# DCF77_RX_1V0.net
KiCad netlist of a schematic drawn in EAGLE
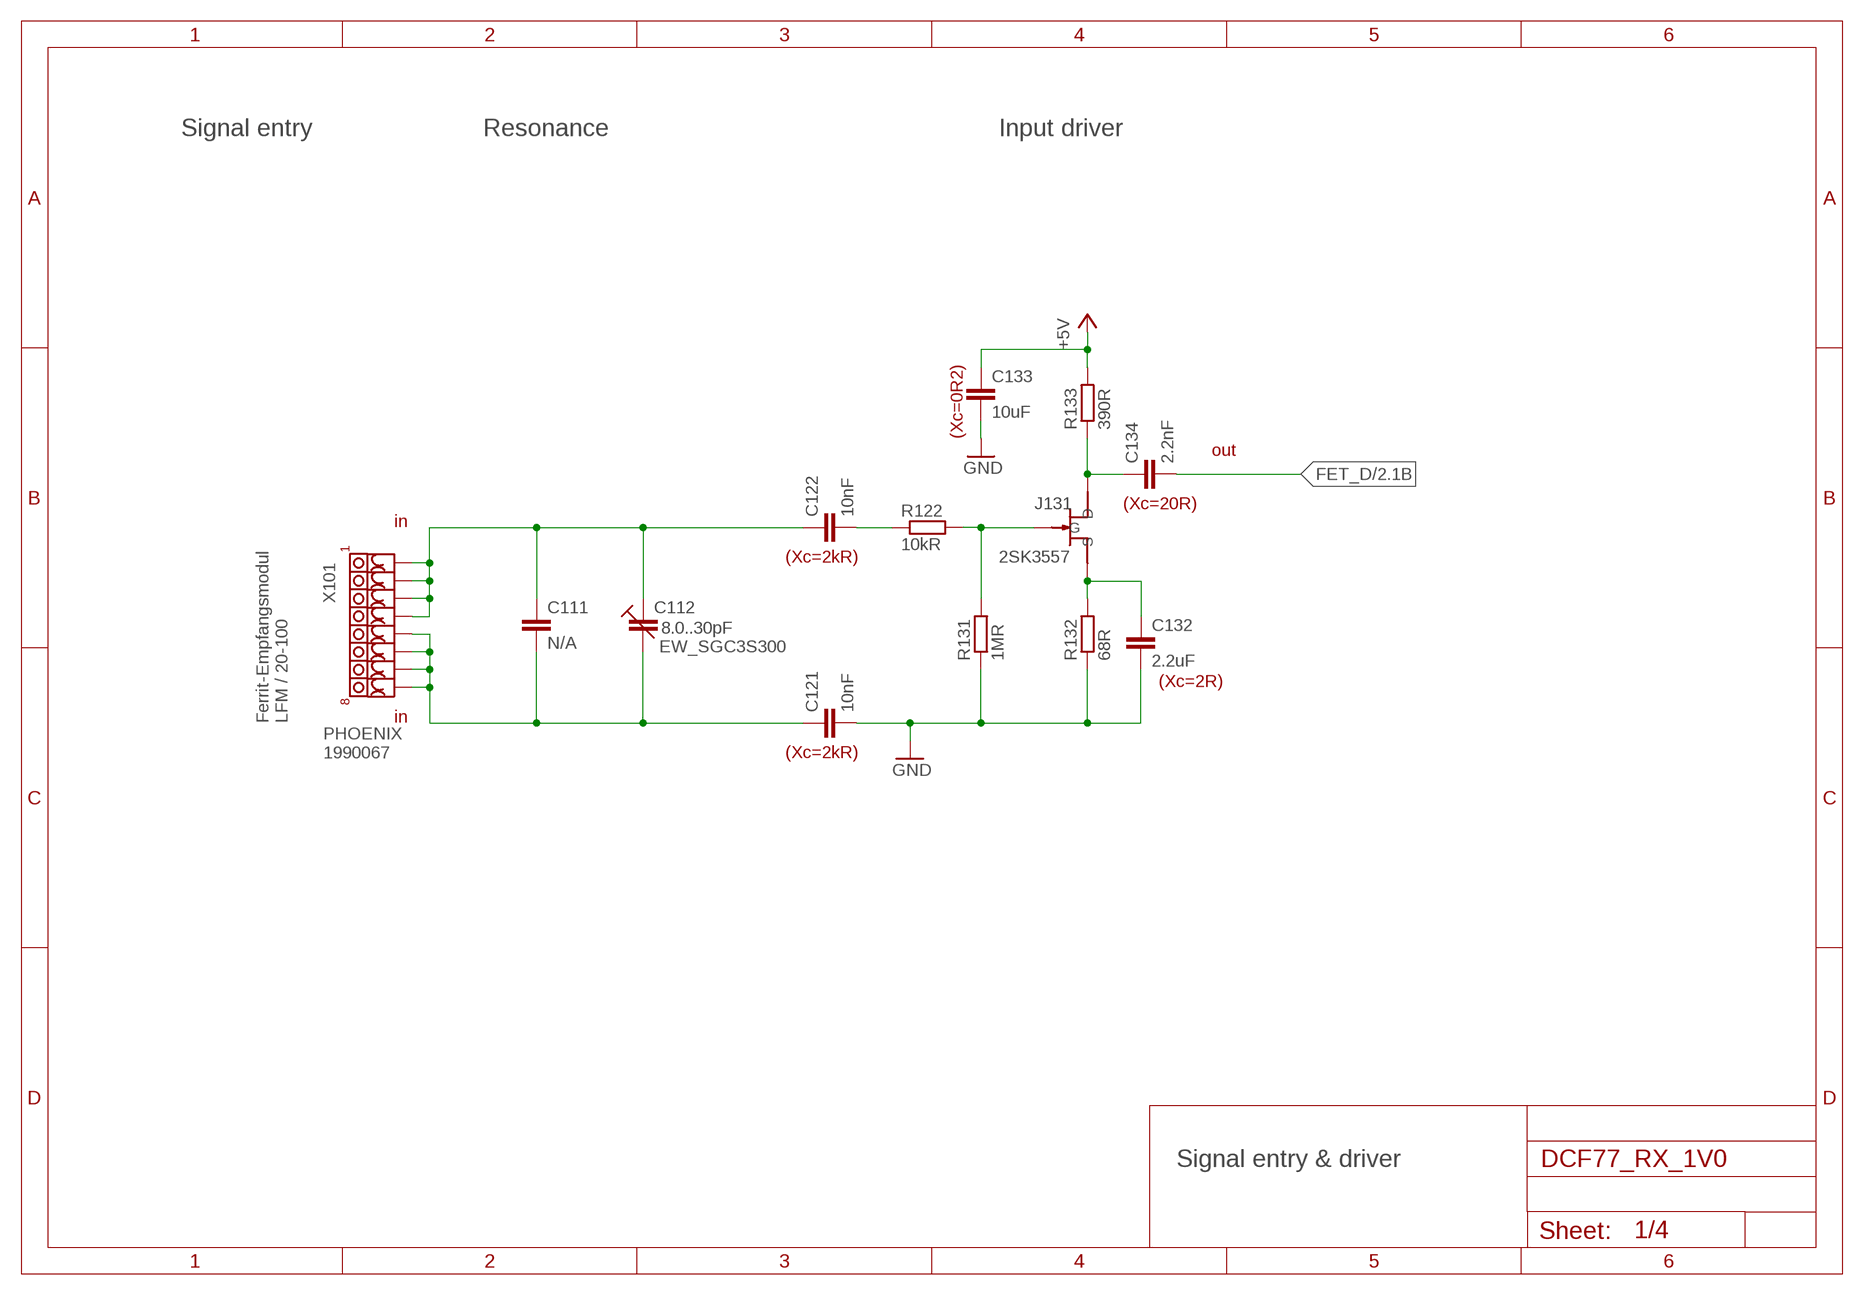
[diagram p0: schematic, sheet 1]
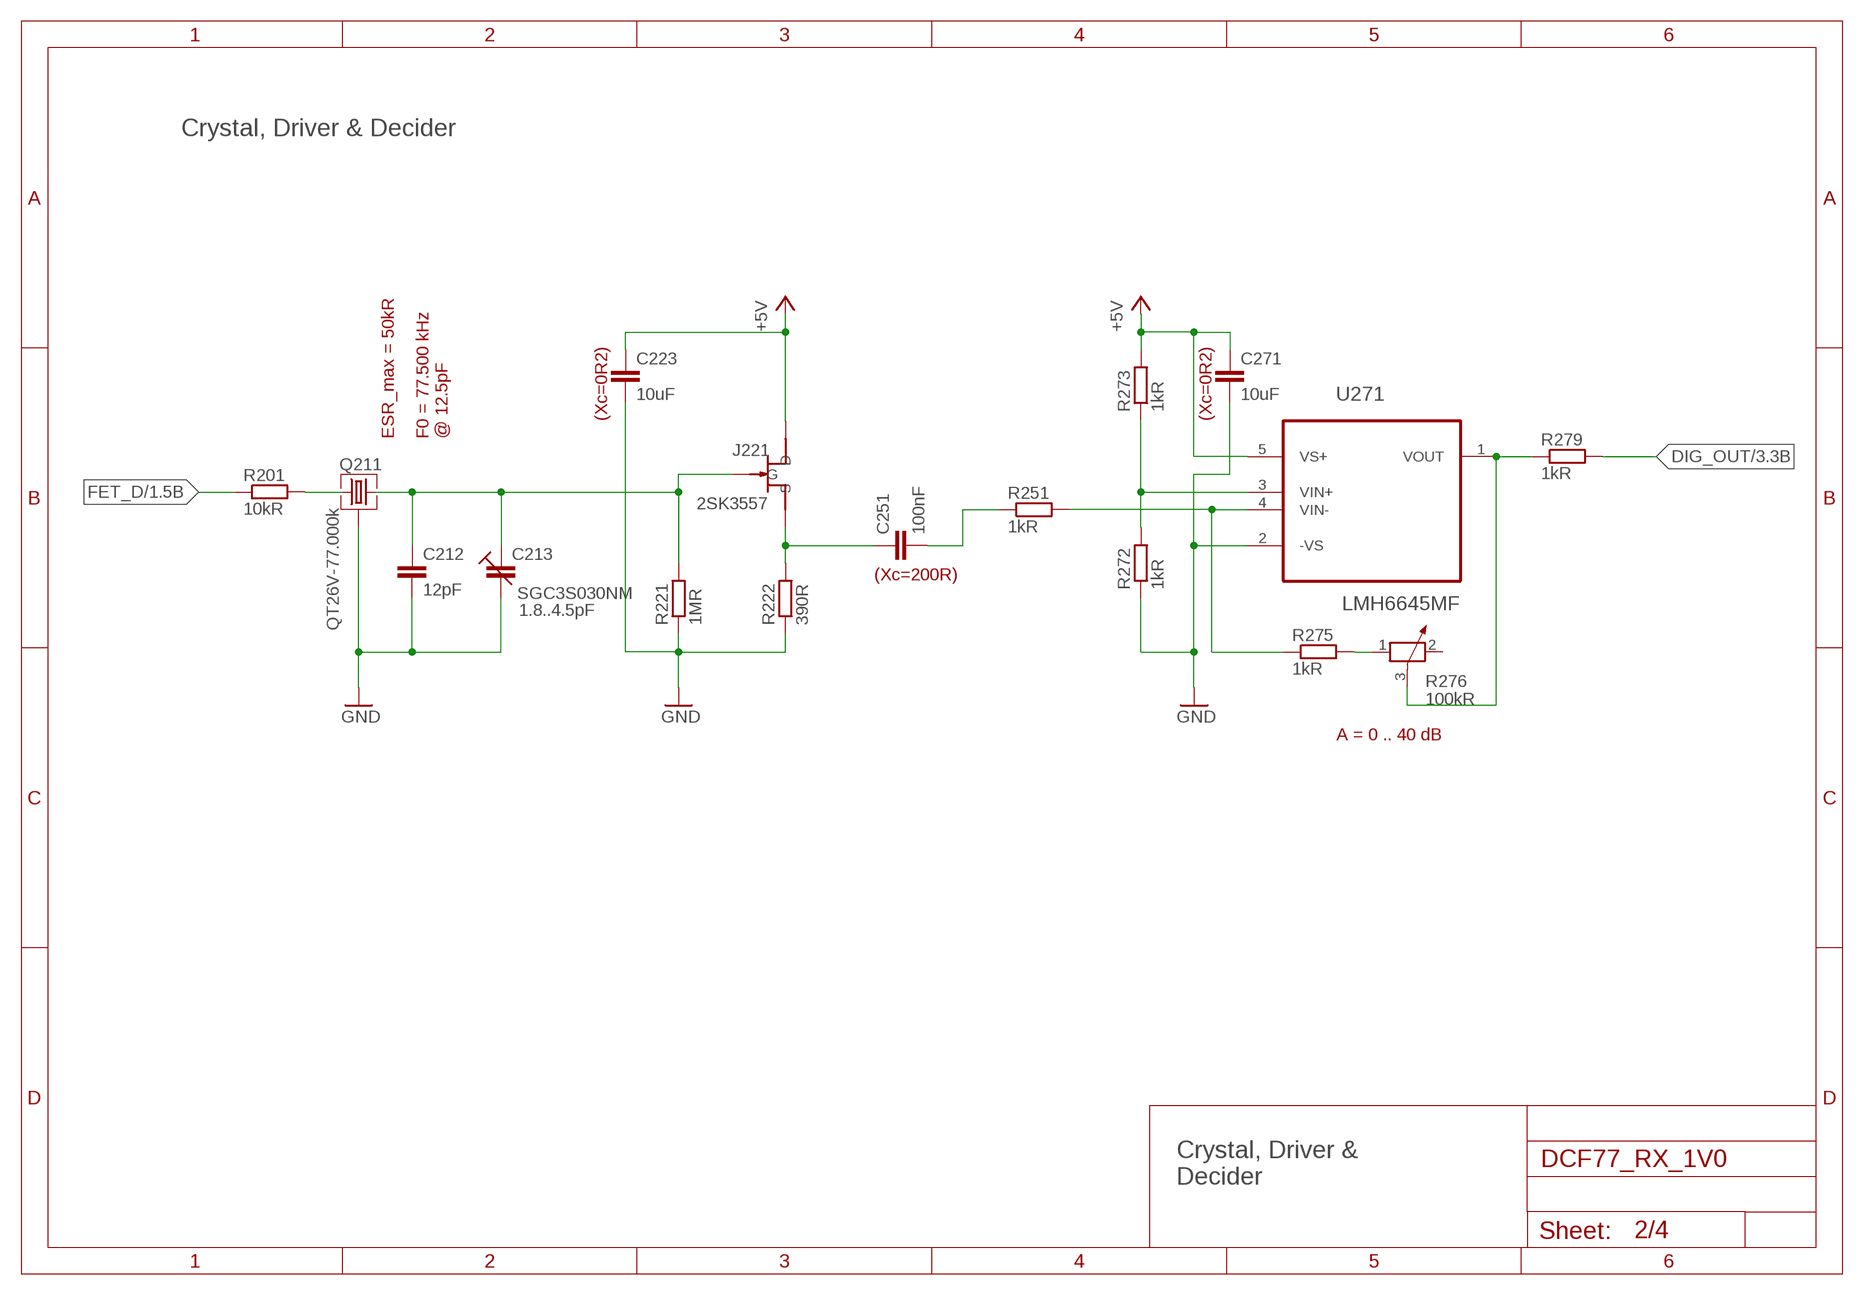
[diagram p1: schematic, sheet 2]
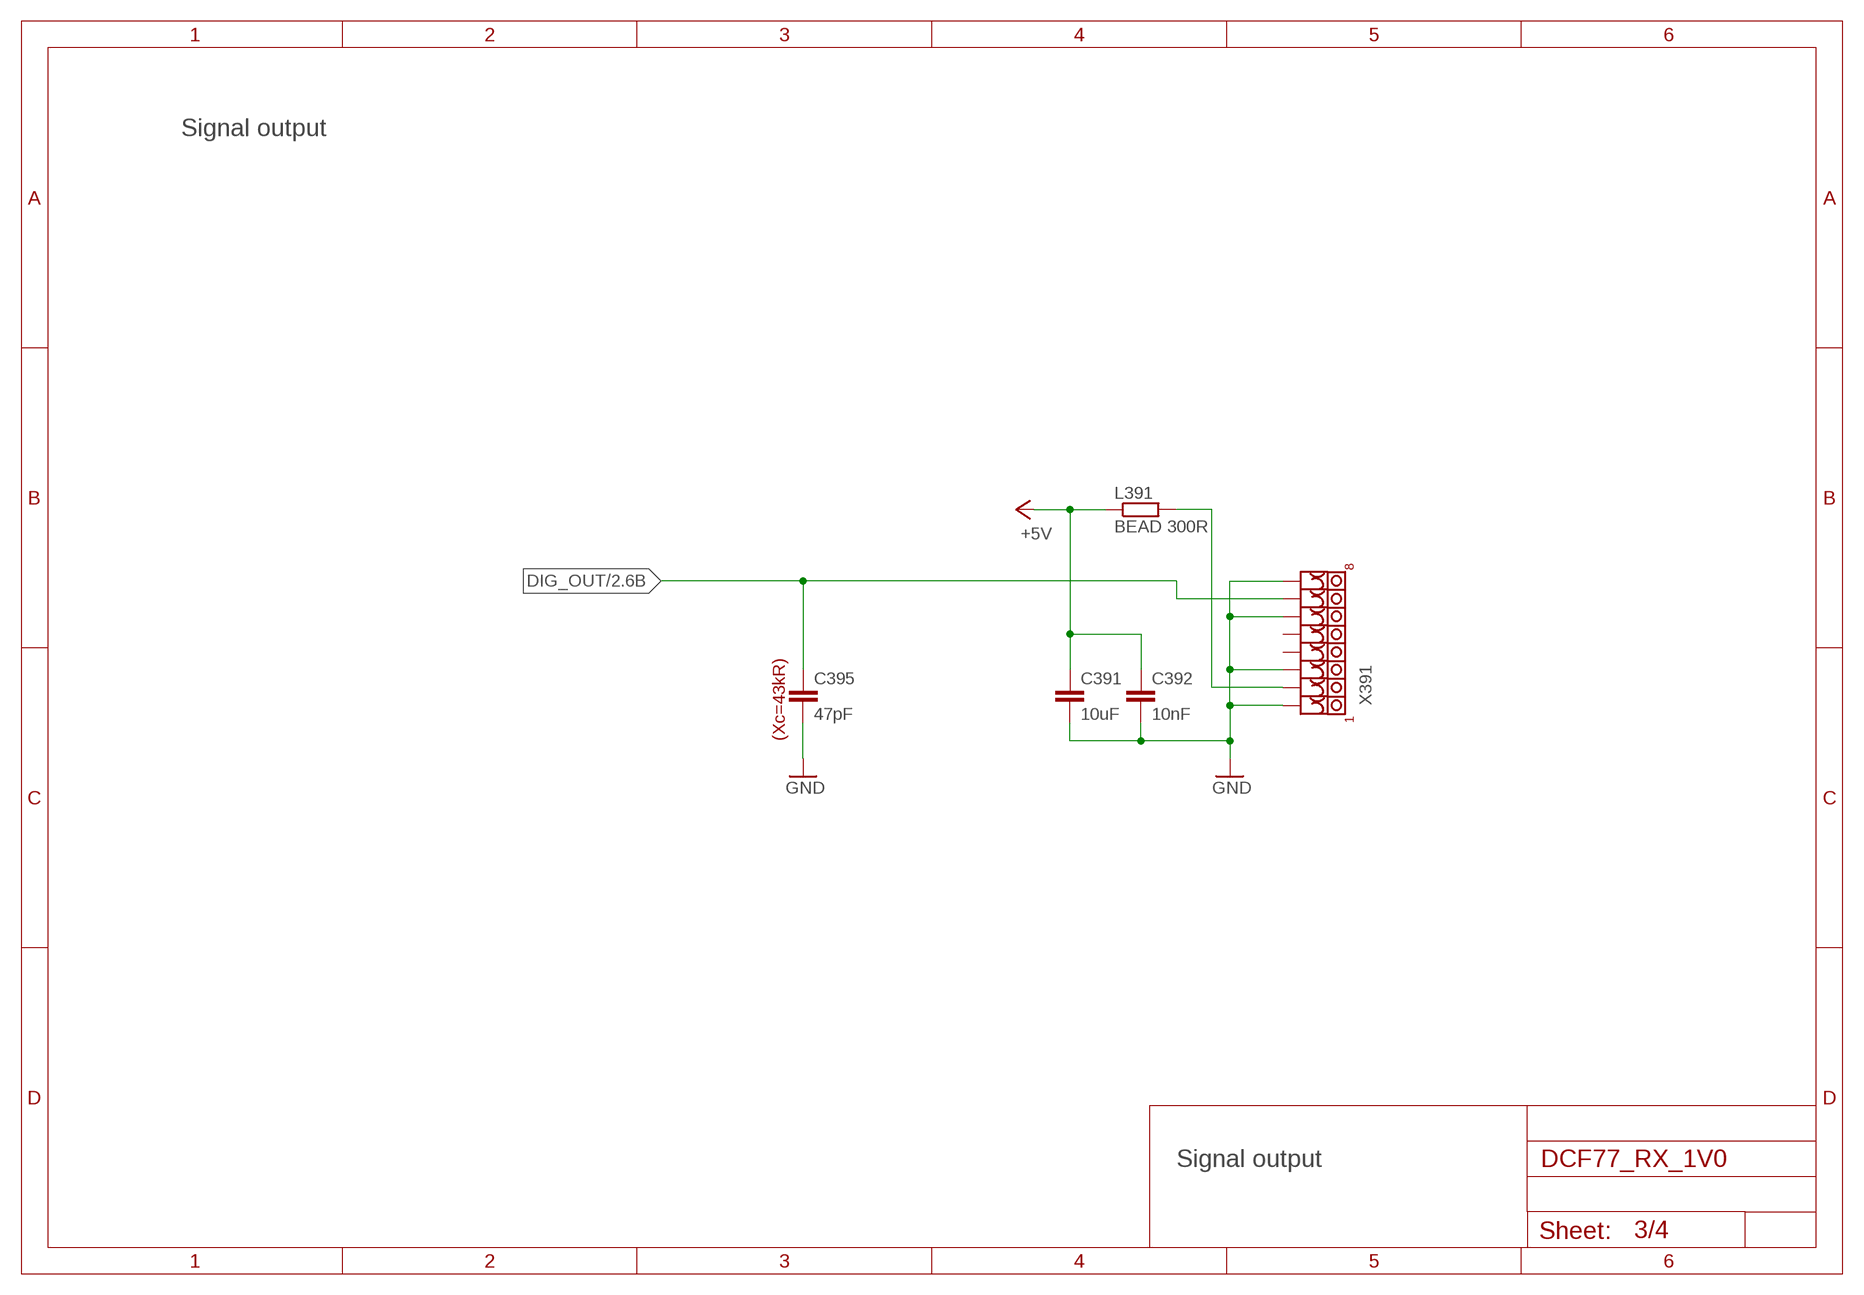
[diagram p2: schematic, sheet 3]
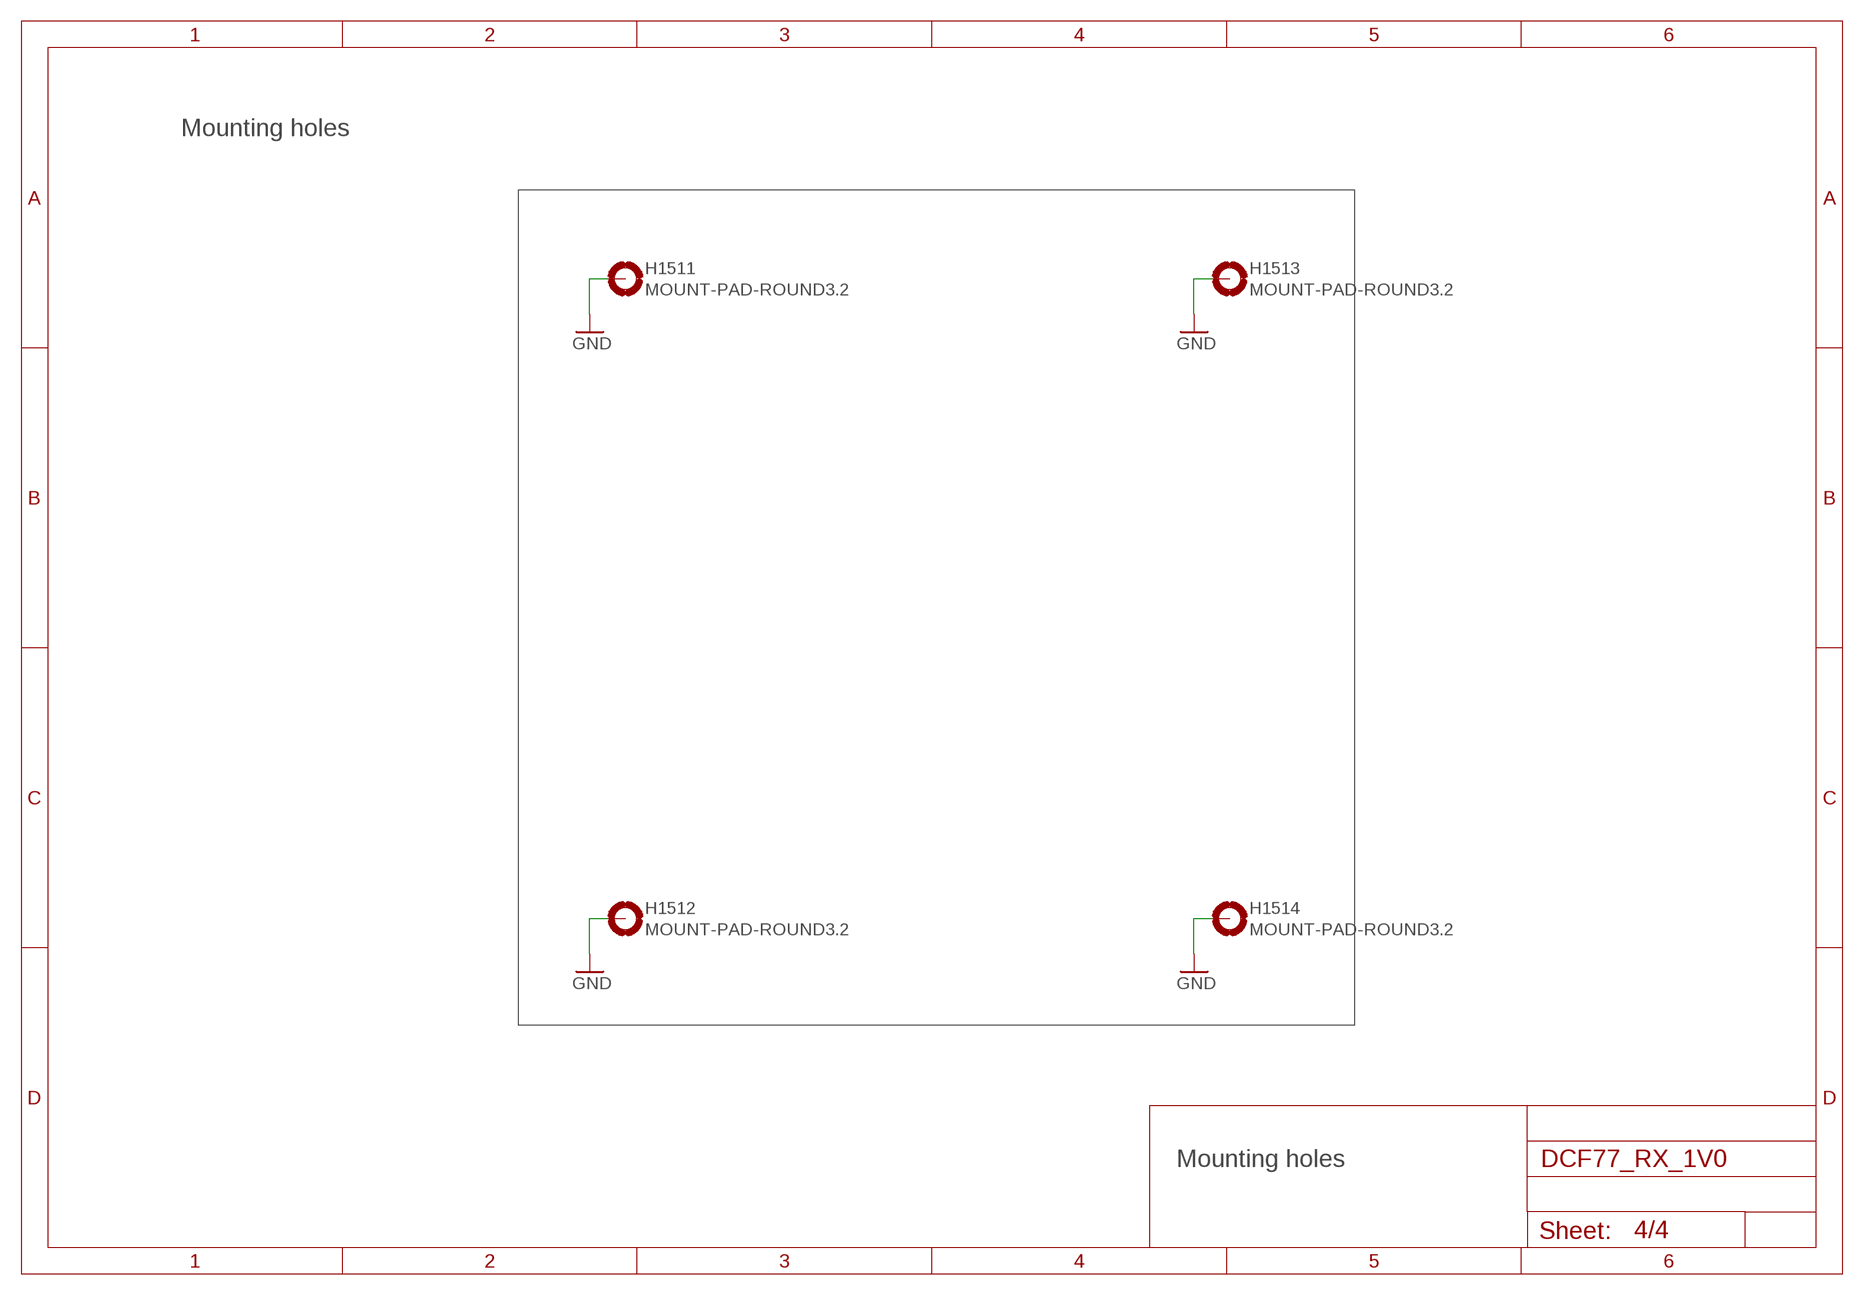
[diagram p3: schematic, sheet 4]

(export (version "E")
  (design (tool "Eeschema 10.0.6"))
  (components
    (comp (ref "C111")
      (value "N/A")
      (footprint "eagle-import:C0402")
      (libsource (lib "eagle-import") (part "C-EUC0402"))
    )
    (comp (ref "C112")
      (value "EW_SGC3S300")
      (footprint "eagle-import:4MM5_X_3MM2__EW_SGC3S")
      (libsource (lib "eagle-import") (part "C-TRIMM__EW_SGC3S"))
    )
    (comp (ref "C121")
      (value "10nF")
      (footprint "eagle-import:C0805")
      (libsource (lib "eagle-import") (part "C-EUC0805"))
    )
    (comp (ref "C122")
      (value "10nF")
      (footprint "eagle-import:C0805")
      (libsource (lib "eagle-import") (part "C-EUC0805"))
    )
    (comp (ref "C132")
      (value "2.2uF")
      (footprint "eagle-import:C0805")
      (libsource (lib "eagle-import") (part "C-EUC0805"))
    )
    (comp (ref "C133")
      (value "10uF")
      (footprint "eagle-import:C0805")
      (libsource (lib "eagle-import") (part "C-EUC0805"))
    )
    (comp (ref "C134")
      (value "2.2nF")
      (footprint "eagle-import:C0805")
      (libsource (lib "eagle-import") (part "C-EUC0805"))
    )
    (comp (ref "J131")
      (value "2SK3557")
      (footprint "eagle-import:SOT23-3")
      (libsource (lib "eagle-import") (part "2SK3557_N-JFET"))
    )
    (comp (ref "R122")
      (value "10kR")
      (footprint "eagle-import:R0805")
      (libsource (lib "eagle-import") (part "R-EU_R0805"))
    )
    (comp (ref "R131")
      (value "1MR")
      (footprint "eagle-import:R0805")
      (libsource (lib "eagle-import") (part "R-EU_R0805"))
    )
    (comp (ref "R132")
      (value "68R")
      (footprint "eagle-import:R0805")
      (libsource (lib "eagle-import") (part "R-EU_R0805"))
    )
    (comp (ref "R133")
      (value "390R")
      (footprint "eagle-import:R0805")
      (libsource (lib "eagle-import") (part "R-EU_R0805"))
    )
    (comp (ref "X101")
      (value "PHOENIX_1990067_1X8X2MM50_PTSA-0-5")
      (footprint "eagle-import:PHOENIX_1990067_1X8X2MM50_PTSA-0-5")
      (libsource (lib "eagle-import") (part "PHOENIX_1990067_1X8X2MM50_PTSA-0-5"))
    )
    (comp (ref "H1511")
      (value "MOUNT-PAD-ROUND3.2")
      (footprint "eagle-import:3,2-PAD")
      (libsource (lib "eagle-import") (part "MOUNT-PAD-ROUND3.2"))
    )
    (comp (ref "H1512")
      (value "MOUNT-PAD-ROUND3.2")
      (footprint "eagle-import:3,2-PAD")
      (libsource (lib "eagle-import") (part "MOUNT-PAD-ROUND3.2"))
    )
    (comp (ref "H1513")
      (value "MOUNT-PAD-ROUND3.2")
      (footprint "eagle-import:3,2-PAD")
      (libsource (lib "eagle-import") (part "MOUNT-PAD-ROUND3.2"))
    )
    (comp (ref "H1514")
      (value "MOUNT-PAD-ROUND3.2")
      (footprint "eagle-import:3,2-PAD")
      (libsource (lib "eagle-import") (part "MOUNT-PAD-ROUND3.2"))
    )
    (comp (ref "C212")
      (value "12pF")
      (footprint "eagle-import:C0402")
      (libsource (lib "eagle-import") (part "C-EUC0402"))
    )
    (comp (ref "C213")
      (value "SGC3S030NM")
      (footprint "eagle-import:4MM5_X_3MM2__EW_SGC3S")
      (libsource (lib "eagle-import") (part "C-TRIMM__EW_SGC3S"))
    )
    (comp (ref "C223")
      (value "10uF")
      (footprint "eagle-import:C0805")
      (libsource (lib "eagle-import") (part "C-EUC0805"))
    )
    (comp (ref "C251")
      (value "100nF")
      (footprint "eagle-import:C0805")
      (libsource (lib "eagle-import") (part "C-EUC0805"))
    )
    (comp (ref "C271")
      (value "10uF")
      (footprint "eagle-import:C0805")
      (libsource (lib "eagle-import") (part "C-EUC0805"))
    )
    (comp (ref "J221")
      (value "2SK3557")
      (footprint "eagle-import:SOT23-3")
      (libsource (lib "eagle-import") (part "2SK3557_N-JFET"))
    )
    (comp (ref "Q211")
      (value "QT26V-77.000k")
      (footprint "eagle-import:QT26V_QST")
      (libsource (lib "eagle-import") (part "QST_QT26V_77.5KHZ"))
    )
    (comp (ref "R201")
      (value "10kR")
      (footprint "eagle-import:R0805")
      (libsource (lib "eagle-import") (part "R-EU_R0805"))
    )
    (comp (ref "R221")
      (value "1MR")
      (footprint "eagle-import:R0805")
      (libsource (lib "eagle-import") (part "R-EU_R0805"))
    )
    (comp (ref "R222")
      (value "390R")
      (footprint "eagle-import:R0805")
      (libsource (lib "eagle-import") (part "R-EU_R0805"))
    )
    (comp (ref "R251")
      (value "1kR")
      (footprint "eagle-import:R0805")
      (libsource (lib "eagle-import") (part "R-EU_R0805"))
    )
    (comp (ref "R272")
      (value "1kR")
      (footprint "eagle-import:R0805")
      (libsource (lib "eagle-import") (part "R-EU_R0805"))
    )
    (comp (ref "R273")
      (value "1kR")
      (footprint "eagle-import:R0805")
      (libsource (lib "eagle-import") (part "R-EU_R0805"))
    )
    (comp (ref "R275")
      (value "1kR")
      (footprint "eagle-import:R0805")
      (libsource (lib "eagle-import") (part "R-EU_R0805"))
    )
    (comp (ref "R276")
      (value "100kR")
      (footprint "eagle-import:PT-10")
      (libsource (lib "eagle-import") (part "POTENTIOMETER_PT-10"))
    )
    (comp (ref "R279")
      (value "1kR")
      (footprint "eagle-import:R0805")
      (libsource (lib "eagle-import") (part "R-EU_R0805"))
    )
    (comp (ref "U271")
      (value "LMH6645MF")
      (footprint "eagle-import:SOT-23-5")
      (libsource (lib "eagle-import") (part "LMH6645MF"))
    )
    (comp (ref "C391")
      (value "10uF")
      (footprint "eagle-import:C0805")
      (libsource (lib "eagle-import") (part "C-EUC0805"))
    )
    (comp (ref "C392")
      (value "10nF")
      (footprint "eagle-import:C0805")
      (libsource (lib "eagle-import") (part "C-EUC0805"))
    )
    (comp (ref "C395")
      (value "47pF")
      (footprint "eagle-import:C0805")
      (libsource (lib "eagle-import") (part "C-EUC0805"))
    )
    (comp (ref "L391")
      (value "BEAD 300R")
      (footprint "eagle-import:R1206")
      (libsource (lib "eagle-import") (part "R-EU_R1206"))
    )
    (comp (ref "X391")
      (value "PHOENIX_1990067_1X8X2MM50_PTSA-0-5")
      (footprint "eagle-import:PHOENIX_1990067_1X8X2MM50_PTSA-0-5")
      (libsource (lib "eagle-import") (part "PHOENIX_1990067_1X8X2MM50_PTSA-0-5"))
    )
  )
  (nets
    (net (code "1") (name "+5V") (class "Default")
      (node (ref "C133") (pin "1") (pinfunction "1_1") (pintype "passive"))
      (node (ref "C223") (pin "1") (pinfunction "1_1") (pintype "passive"))
      (node (ref "C271") (pin "1") (pinfunction "1_1") (pintype "passive"))
      (node (ref "C391") (pin "1") (pinfunction "1_1") (pintype "passive"))
      (node (ref "C392") (pin "1") (pinfunction "1_1") (pintype "passive"))
      (node (ref "J221") (pin "P$2") (pinfunction "D_P$2") (pintype "passive"))
      (node (ref "L391") (pin "1") (pinfunction "1_1") (pintype "passive"))
      (node (ref "R133") (pin "2") (pinfunction "2_2") (pintype "passive"))
      (node (ref "R273") (pin "2") (pinfunction "2_2") (pintype "passive"))
      (node (ref "U271") (pin "5") (pinfunction "VS+_5") (pintype "power_in"))
    )
    (net (code "2") (name "DIG_OUT") (class "Default")
      (node (ref "C395") (pin "1") (pinfunction "1_1") (pintype "passive"))
      (node (ref "R279") (pin "2") (pinfunction "2_2") (pintype "passive"))
      (node (ref "X391") (pin "7") (pinfunction "7_7") (pintype "passive"))
    )
    (net (code "3") (name "FET_D") (class "Default")
      (node (ref "C134") (pin "2") (pinfunction "2_2") (pintype "passive"))
      (node (ref "R201") (pin "1") (pinfunction "1_1") (pintype "passive"))
    )
    (net (code "4") (name "GND") (class "Default")
      (node (ref "C121") (pin "2") (pinfunction "2_2") (pintype "passive"))
      (node (ref "C132") (pin "2") (pinfunction "2_2") (pintype "passive"))
      (node (ref "C133") (pin "2") (pinfunction "2_2") (pintype "passive"))
      (node (ref "C212") (pin "2") (pinfunction "2_2") (pintype "passive"))
      (node (ref "C213") (pin "CSTAT") (pinfunction "CSTAT_CSTAT") (pintype "passive"))
      (node (ref "C223") (pin "2") (pinfunction "2_2") (pintype "passive"))
      (node (ref "C271") (pin "2") (pinfunction "2_2") (pintype "passive"))
      (node (ref "C391") (pin "2") (pinfunction "2_2") (pintype "passive"))
      (node (ref "C392") (pin "2") (pinfunction "2_2") (pintype "passive"))
      (node (ref "C395") (pin "2") (pinfunction "2_2") (pintype "passive"))
      (node (ref "H1511") (pin "B3,2") (pinfunction "MOUNT_B3,2") (pintype "passive"))
      (node (ref "H1512") (pin "B3,2") (pinfunction "MOUNT_B3,2") (pintype "passive"))
      (node (ref "H1513") (pin "B3,2") (pinfunction "MOUNT_B3,2") (pintype "passive"))
      (node (ref "H1514") (pin "B3,2") (pinfunction "MOUNT_B3,2") (pintype "passive"))
      (node (ref "Q211") (pin "3") (pinfunction "3_3") (pintype "passive"))
      (node (ref "Q211") (pin "4") (pinfunction "3_4") (pintype "passive"))
      (node (ref "R131") (pin "1") (pinfunction "1_1") (pintype "passive"))
      (node (ref "R132") (pin "1") (pinfunction "1_1") (pintype "passive"))
      (node (ref "R221") (pin "1") (pinfunction "1_1") (pintype "passive"))
      (node (ref "R222") (pin "1") (pinfunction "1_1") (pintype "passive"))
      (node (ref "R272") (pin "1") (pinfunction "1_1") (pintype "passive"))
      (node (ref "U271") (pin "2") (pinfunction "-VS_2") (pintype "power_in"))
      (node (ref "X391") (pin "1") (pinfunction "1_1") (pintype "passive"))
      (node (ref "X391") (pin "3") (pinfunction "3_3") (pintype "passive"))
      (node (ref "X391") (pin "6") (pinfunction "6_6") (pintype "passive"))
      (node (ref "X391") (pin "8") (pinfunction "8_8") (pintype "passive"))
    )
    (net (code "5") (name "Net-(C111-Pad1)") (class "Default")
      (node (ref "C111") (pin "1") (pinfunction "1_1") (pintype "passive"))
      (node (ref "C112") (pin "CROT") (pinfunction "CROT_CROT") (pintype "passive"))
      (node (ref "C122") (pin "1") (pinfunction "1_1") (pintype "passive"))
      (node (ref "X101") (pin "1") (pinfunction "1_1") (pintype "passive"))
      (node (ref "X101") (pin "2") (pinfunction "2_2") (pintype "passive"))
      (node (ref "X101") (pin "3") (pinfunction "3_3") (pintype "passive"))
      (node (ref "X101") (pin "4") (pinfunction "4_4") (pintype "passive"))
    )
    (net (code "6") (name "Net-(C111-Pad2)") (class "Default")
      (node (ref "C111") (pin "2") (pinfunction "2_2") (pintype "passive"))
      (node (ref "C112") (pin "CSTAT") (pinfunction "CSTAT_CSTAT") (pintype "passive"))
      (node (ref "C121") (pin "1") (pinfunction "1_1") (pintype "passive"))
      (node (ref "X101") (pin "5") (pinfunction "5_5") (pintype "passive"))
      (node (ref "X101") (pin "6") (pinfunction "6_6") (pintype "passive"))
      (node (ref "X101") (pin "7") (pinfunction "7_7") (pintype "passive"))
      (node (ref "X101") (pin "8") (pinfunction "8_8") (pintype "passive"))
    )
    (net (code "7") (name "Net-(C122-Pad2)") (class "Default")
      (node (ref "C122") (pin "2") (pinfunction "2_2") (pintype "passive"))
      (node (ref "R122") (pin "1") (pinfunction "1_1") (pintype "passive"))
    )
    (net (code "8") (name "Net-(C251-Pad2)") (class "Default")
      (node (ref "C251") (pin "2") (pinfunction "2_2") (pintype "passive"))
      (node (ref "R251") (pin "1") (pinfunction "1_1") (pintype "passive"))
    )
    (net (code "9") (name "Net-(J131-D)") (class "Default")
      (node (ref "C134") (pin "1") (pinfunction "1_1") (pintype "passive"))
      (node (ref "J131") (pin "P$2") (pinfunction "D_P$2") (pintype "passive"))
      (node (ref "R133") (pin "1") (pinfunction "1_1") (pintype "passive"))
    )
    (net (code "10") (name "Net-(J131-G)") (class "Default")
      (node (ref "J131") (pin "P$3") (pinfunction "G_P$3") (pintype "passive"))
      (node (ref "R122") (pin "2") (pinfunction "2_2") (pintype "passive"))
      (node (ref "R131") (pin "2") (pinfunction "2_2") (pintype "passive"))
    )
    (net (code "11") (name "Net-(J131-S)") (class "Default")
      (node (ref "C132") (pin "1") (pinfunction "1_1") (pintype "passive"))
      (node (ref "J131") (pin "P$1") (pinfunction "S_P$1") (pintype "passive"))
      (node (ref "R132") (pin "2") (pinfunction "2_2") (pintype "passive"))
    )
    (net (code "12") (name "Net-(J221-G)") (class "Default")
      (node (ref "C212") (pin "1") (pinfunction "1_1") (pintype "passive"))
      (node (ref "C213") (pin "CROT") (pinfunction "CROT_CROT") (pintype "passive"))
      (node (ref "J221") (pin "P$3") (pinfunction "G_P$3") (pintype "passive"))
      (node (ref "Q211") (pin "2") (pinfunction "2_2") (pintype "passive"))
      (node (ref "R221") (pin "2") (pinfunction "2_2") (pintype "passive"))
    )
    (net (code "13") (name "Net-(J221-S)") (class "Default")
      (node (ref "C251") (pin "1") (pinfunction "1_1") (pintype "passive"))
      (node (ref "J221") (pin "P$1") (pinfunction "S_P$1") (pintype "passive"))
      (node (ref "R222") (pin "2") (pinfunction "2_2") (pintype "passive"))
    )
    (net (code "14") (name "Net-(L391-Pad2)") (class "Default")
      (node (ref "L391") (pin "2") (pinfunction "2_2") (pintype "passive"))
      (node (ref "X391") (pin "2") (pinfunction "2_2") (pintype "passive"))
    )
    (net (code "15") (name "Net-(Q211-Pad1)") (class "Default")
      (node (ref "Q211") (pin "1") (pinfunction "1_1") (pintype "passive"))
      (node (ref "R201") (pin "2") (pinfunction "2_2") (pintype "passive"))
    )
    (net (code "16") (name "Net-(R275-Pad2)") (class "Default")
      (node (ref "R275") (pin "2") (pinfunction "2_2") (pintype "passive"))
      (node (ref "R276") (pin "1") (pinfunction "1_1") (pintype "passive"))
    )
    (net (code "17") (name "Net-(U271-VIN+)") (class "Default")
      (node (ref "R272") (pin "2") (pinfunction "2_2") (pintype "passive"))
      (node (ref "R273") (pin "1") (pinfunction "1_1") (pintype "passive"))
      (node (ref "U271") (pin "3") (pinfunction "VIN+_3") (pintype "input"))
    )
    (net (code "18") (name "Net-(U271-VIN-)") (class "Default")
      (node (ref "R251") (pin "2") (pinfunction "2_2") (pintype "passive"))
      (node (ref "R275") (pin "1") (pinfunction "1_1") (pintype "passive"))
      (node (ref "U271") (pin "4") (pinfunction "VIN-_4") (pintype "input"))
    )
    (net (code "19") (name "Net-(U271-VOUT)") (class "Default")
      (node (ref "R276") (pin "3") (pinfunction "3_3") (pintype "passive"))
      (node (ref "R279") (pin "1") (pinfunction "1_1") (pintype "passive"))
      (node (ref "U271") (pin "1") (pinfunction "VOUT_1") (pintype "output"))
    )
    (net (code "20") (name "unconnected-(R276-Pad2)") (class "Default")
      (node (ref "R276") (pin "2") (pinfunction "2_2") (pintype "passive"))
    )
    (net (code "21") (name "unconnected-(X391-Pad4)") (class "Default")
      (node (ref "X391") (pin "4") (pinfunction "4_4") (pintype "passive"))
    )
    (net (code "22") (name "unconnected-(X391-Pad5)") (class "Default")
      (node (ref "X391") (pin "5") (pinfunction "5_5") (pintype "passive"))
    )
  )
)
